# ESP32.net
KiCad netlist of a schematic drawn in Altium Designer
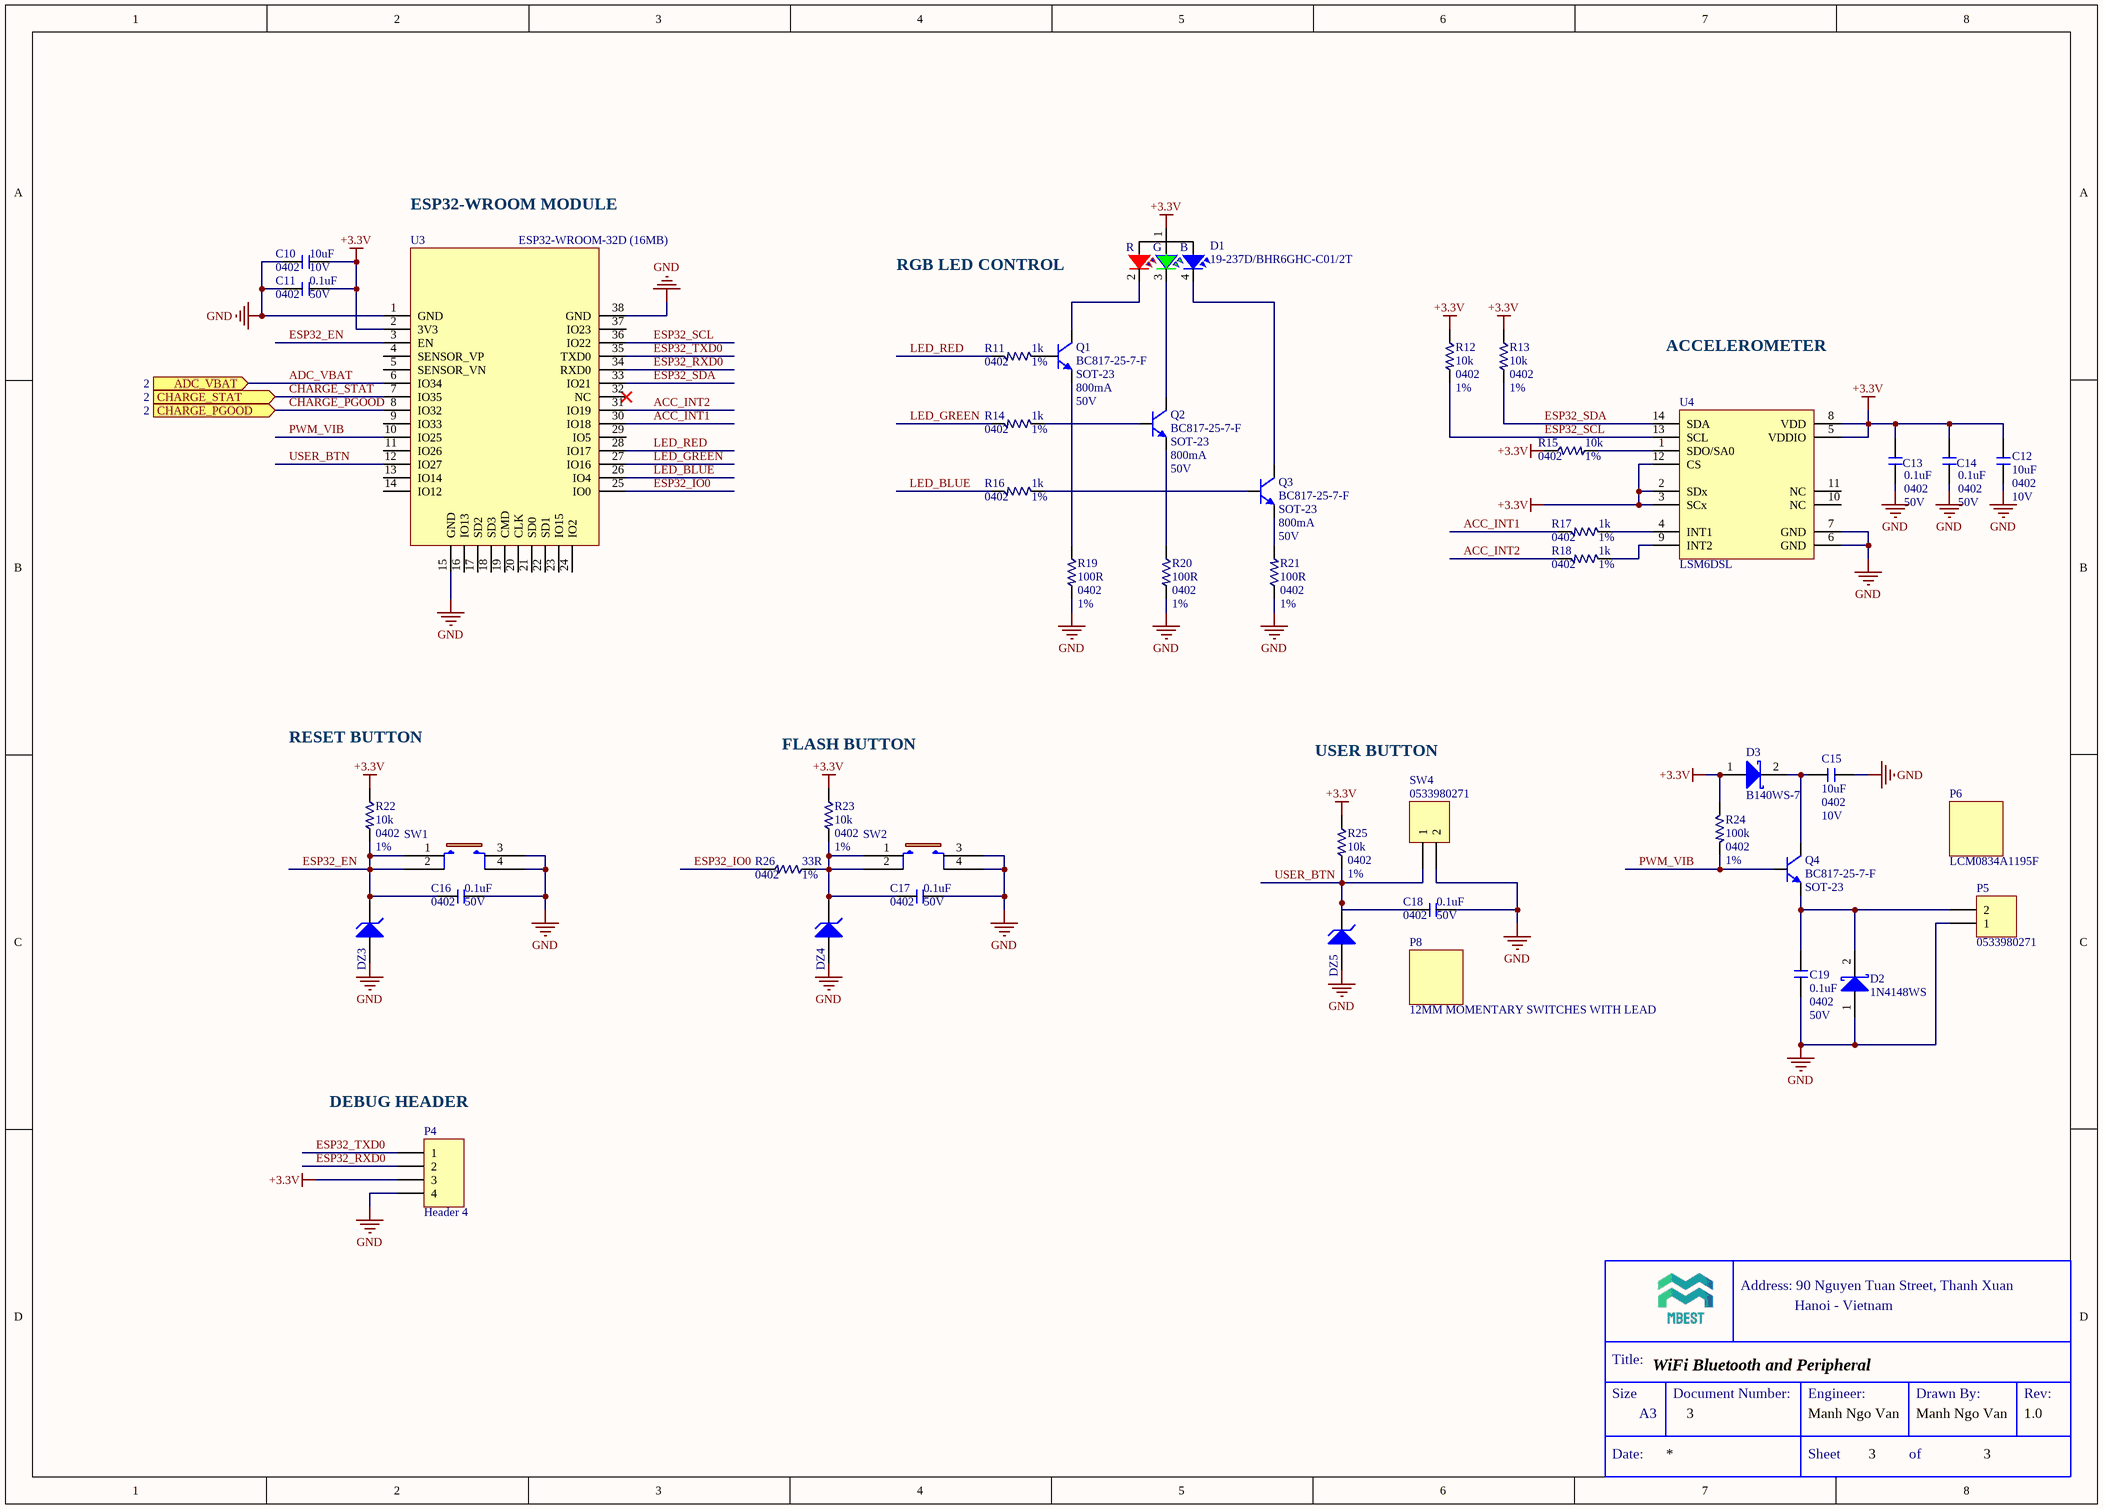
[diagram p0: ESP32.SchDoc]

(export (version "E")
  (design (tool "Eeschema 10.0.6"))
  (components
    (comp (ref "C10")
      (value "10uF")
      (footprint "C0402M")
      (description "CAP CER 10UF 10V X5R 0402")
      (fields
        (field (name "CASE/PACKAGE") "0402")
        (field (name "VOLTAGE RATING") "10V")
        (field (name "TOLERANCE") "20%")
      )
      (libsource (lib "") (part "CAP_CER_1"))
    )
    (comp (ref "C11")
      (value "0.1uF")
      (footprint "C0402M")
      (description "CAP CER 0.1UF 50V X7R 0402")
      (fields
        (field (name "MANUFACTURER") "Murata")
        (field (name "MANUFACTURER PART NUMBER") "GRM155R71H104KE14D")
        (field (name "CASE/PACKAGE") "0402")
        (field (name "VOLTAGE") "50V")
      )
      (libsource (lib "CommonLib") (part "CAP_CER"))
    )
    (comp (ref "C12")
      (value "10uF")
      (footprint "C0402M")
      (description "CAP CER 10UF 10V X5R 0402")
      (fields
        (field (name "CASE/PACKAGE") "0402")
        (field (name "VOLTAGE RATING") "10V")
        (field (name "TOLERANCE") "20%")
      )
      (libsource (lib "") (part "CAP_CER_1"))
    )
    (comp (ref "C13")
      (value "0.1uF")
      (footprint "C0402M")
      (description "CAP CER 0.1UF 50V X7R 0402")
      (fields
        (field (name "MANUFACTURER") "Murata")
        (field (name "MANUFACTURER PART NUMBER") "GRM155R71H104KE14D")
        (field (name "CASE/PACKAGE") "0402")
        (field (name "VOLTAGE") "50V")
      )
      (libsource (lib "CommonLib") (part "CAP_CER"))
    )
    (comp (ref "C14")
      (value "0.1uF")
      (footprint "C0402M")
      (description "CAP CER 0.1UF 50V X7R 0402")
      (fields
        (field (name "MANUFACTURER") "Murata")
        (field (name "MANUFACTURER PART NUMBER") "GRM155R71H104KE14D")
        (field (name "CASE/PACKAGE") "0402")
        (field (name "VOLTAGE") "50V")
      )
      (libsource (lib "CommonLib") (part "CAP_CER"))
    )
    (comp (ref "C15")
      (value "10uF")
      (footprint "C0402M")
      (description "CAP CER 10UF 10V X5R 0402")
      (fields
        (field (name "CASE/PACKAGE") "0402")
        (field (name "VOLTAGE RATING") "10V")
        (field (name "TOLERANCE") "20%")
      )
      (libsource (lib "") (part "CAP_CER_1"))
    )
    (comp (ref "C16")
      (value "0.1uF")
      (footprint "C0402M")
      (description "CAP CER 0.1UF 50V X7R 0402")
      (fields
        (field (name "MANUFACTURER") "Murata")
        (field (name "MANUFACTURER PART NUMBER") "GRM155R71H104KE14D")
        (field (name "CASE/PACKAGE") "0402")
        (field (name "VOLTAGE") "50V")
      )
      (libsource (lib "CommonLib") (part "CAP_CER"))
    )
    (comp (ref "C17")
      (value "0.1uF")
      (footprint "C0402M")
      (description "CAP CER 0.1UF 50V X7R 0402")
      (fields
        (field (name "MANUFACTURER") "Murata")
        (field (name "MANUFACTURER PART NUMBER") "GRM155R71H104KE14D")
        (field (name "CASE/PACKAGE") "0402")
        (field (name "VOLTAGE") "50V")
      )
      (libsource (lib "CommonLib") (part "CAP_CER"))
    )
    (comp (ref "C18")
      (value "0.1uF")
      (footprint "C0402M")
      (description "CAP CER 0.1UF 50V X7R 0402")
      (fields
        (field (name "MANUFACTURER") "Murata")
        (field (name "MANUFACTURER PART NUMBER") "GRM155R71H104KE14D")
        (field (name "CASE/PACKAGE") "0402")
        (field (name "VOLTAGE") "50V")
      )
      (libsource (lib "CommonLib") (part "CAP_CER"))
    )
    (comp (ref "C19")
      (value "0.1uF")
      (footprint "C0402M")
      (description "CAP CER 0.1UF 50V X7R 0402")
      (fields
        (field (name "MANUFACTURER") "Murata")
        (field (name "MANUFACTURER PART NUMBER") "GRM155R71H104KE14D")
        (field (name "CASE/PACKAGE") "0402")
        (field (name "VOLTAGE") "50V")
      )
      (libsource (lib "CommonLib") (part "CAP_CER"))
    )
    (comp (ref "D1")
      (value "19-237D/BHR6GHC-C01/2T")
      (footprint "19-237D/BHR6GHC-C01/2T")
      (description "LED RGB CLEAR 4SMD")
      (libsource (lib "SmartHome") (part "19-237D/BHR6GHC-C01/2T"))
    )
    (comp (ref "D2")
      (value "1N4148WS")
      (footprint "SODFL250X70-2N")
      (description "DIODE GEN PURP 75V 150MA SOD323F")
      (fields (field (name "MANUFACTURER") "ON Semiconductor / Fairchild"))
      (libsource (lib "CommonLib") (part "D Schottky"))
    )
    (comp (ref "D3")
      (value "B140WS-7")
      (footprint "SODFL250X70-2N")
      (description "DIODE SCHOTTKY 40V 1A SOD323")
      (libsource (lib "CommonLib") (part "D Schottky"))
    )
    (comp (ref "DZ3")
      (value "TPD1E10B06DPYR")
      (footprint "R0402M")
      (description "TVS DIODE 5.5V 14V 2X1SON")
      (fields (field (name "MANUFACTURER") "Texas Instruments"))
      (libsource (lib "CommonLib") (part "D Zener"))
    )
    (comp (ref "DZ4")
      (value "TPD1E10B06DPYR")
      (footprint "R0402M")
      (description "TVS DIODE 5.5V 14V 2X1SON")
      (fields (field (name "MANUFACTURER") "Texas Instruments"))
      (libsource (lib "CommonLib") (part "D Zener"))
    )
    (comp (ref "DZ5")
      (value "TPD1E10B06DPYR")
      (footprint "R0402M")
      (description "TVS DIODE 5.5V 14V 2X1SON")
      (fields (field (name "MANUFACTURER") "Texas Instruments"))
      (libsource (lib "CommonLib") (part "D Zener"))
    )
    (comp (ref "P4")
      (value "Header 4")
      (footprint "HDR1X4")
      (description "Header, 4-Pin")
      (fields (field (name "PUBLISHER") "Altium Limited"))
      (libsource (lib "Miscellaneous Connectors") (part "Header 4"))
    )
    (comp (ref "P5")
      (value "0533980271")
      (footprint "0533980271")
      (description "CONN HEADER SMD 2POS 1.25MM")
      (fields (field (name "PUBLISHER") "Altium Limited"))
      (libsource (lib "Miscellaneous Connectors") (part "Header 2"))
    )
    (comp (ref "P6")
      (value "LCM0834A1195F")
      (description "Coin Type Vibration Motor")
      (libsource (lib "CommonLib") (part "ADDITION"))
    )
    (comp (ref "P8")
      (value "12MM MOMENTARY SWITCHES WITH LEAD")
      (libsource (lib "CommonLib") (part "ADDITION"))
    )
    (comp (ref "Q1")
      (value "BC817-25-7-F")
      (footprint "SOT95P245X110-3N")
      (description "TRANS NPN 45V 500MA SOT23-3")
      (fields
        (field (name "CASE/PACKAGE") "SOT-23")
        (field (name "MAX COLLECTOR CURRENT") "800mA")
        (field (name "COLLECTOR BASE VOLTAGE (VCBO)") "50V")
        (field (name "MANUFACTURER") "Diodes")
      )
      (libsource (lib "SmartAC") (part "MMBT3904-7-F"))
    )
    (comp (ref "Q2")
      (value "BC817-25-7-F")
      (footprint "SOT95P245X110-3N")
      (description "TRANS NPN 45V 500MA SOT23-3")
      (fields
        (field (name "CASE/PACKAGE") "SOT-23")
        (field (name "MAX COLLECTOR CURRENT") "800mA")
        (field (name "COLLECTOR BASE VOLTAGE (VCBO)") "50V")
        (field (name "MANUFACTURER") "Diodes")
      )
      (libsource (lib "SmartAC") (part "MMBT3904-7-F"))
    )
    (comp (ref "Q3")
      (value "BC817-25-7-F")
      (footprint "SOT95P245X110-3N")
      (description "TRANS NPN 45V 500MA SOT23-3")
      (fields
        (field (name "CASE/PACKAGE") "SOT-23")
        (field (name "MAX COLLECTOR CURRENT") "800mA")
        (field (name "COLLECTOR BASE VOLTAGE (VCBO)") "50V")
        (field (name "MANUFACTURER") "Diodes")
      )
      (libsource (lib "SmartAC") (part "MMBT3904-7-F"))
    )
    (comp (ref "Q4")
      (value "BC817-25-7-F")
      (footprint "SOT95P245X110-3N")
      (description "TRANS NPN 45V 500MA SOT23-3")
      (fields (field (name "CASE/PACKAGE") "SOT-23") (field (name "MANUFACTURER") "Diodes"))
      (libsource (lib "SmartAC") (part "MMBT3904-7-F"))
    )
    (comp (ref "R11")
      (value "1k")
      (footprint "R0402M")
      (description "RES SMD 1K OHM 1% 1/16W 0402")
      (fields (field (name "CASE/PACKAGE") "0402") (field (name "TOLERANCE") "1%"))
      (libsource (lib "CommonLib") (part "RES_SMD"))
    )
    (comp (ref "R12")
      (value "10k")
      (footprint "R0402M")
      (description "RES SMD 10K OHM 1% 1/16W 0402")
      (fields
        (field (name "MANUFACTURER") "Yageo")
        (field (name "MANUFACTURER PART NUMBER") "RC0402FR-0710KL")
        (field (name "CASE CODE (IMPERIAL)") "0402")
        (field (name "TOLERANCE") "1%")
      )
      (libsource (lib "CommonLib") (part "RES_SMD"))
    )
    (comp (ref "R13")
      (value "10k")
      (footprint "R0402M")
      (description "RES SMD 10K OHM 1% 1/16W 0402")
      (fields
        (field (name "MANUFACTURER") "Yageo")
        (field (name "MANUFACTURER PART NUMBER") "RC0402FR-0710KL")
        (field (name "CASE CODE (IMPERIAL)") "0402")
        (field (name "TOLERANCE") "1%")
      )
      (libsource (lib "CommonLib") (part "RES_SMD"))
    )
    (comp (ref "R14")
      (value "1k")
      (footprint "R0402M")
      (description "RES SMD 1K OHM 1% 1/16W 0402")
      (fields (field (name "CASE/PACKAGE") "0402") (field (name "TOLERANCE") "1%"))
      (libsource (lib "CommonLib") (part "RES_SMD"))
    )
    (comp (ref "R15")
      (value "10k")
      (footprint "R0402M")
      (description "RES SMD 10K OHM 1% 1/16W 0402")
      (fields
        (field (name "MANUFACTURER") "Yageo")
        (field (name "MANUFACTURER PART NUMBER") "RC0402FR-0710KL")
        (field (name "CASE CODE (IMPERIAL)") "0402")
        (field (name "TOLERANCE") "1%")
      )
      (libsource (lib "CommonLib") (part "RES_SMD"))
    )
    (comp (ref "R16")
      (value "1k")
      (footprint "R0402M")
      (description "RES SMD 1K OHM 1% 1/16W 0402")
      (fields (field (name "CASE/PACKAGE") "0402") (field (name "TOLERANCE") "1%"))
      (libsource (lib "CommonLib") (part "RES_SMD"))
    )
    (comp (ref "R17")
      (value "1k")
      (footprint "R0402M")
      (description "RES SMD 1K OHM 1% 1/16W 0402")
      (fields (field (name "CASE/PACKAGE") "0402") (field (name "TOLERANCE") "1%"))
      (libsource (lib "CommonLib") (part "RES_SMD"))
    )
    (comp (ref "R18")
      (value "1k")
      (footprint "R0402M")
      (description "RES SMD 1K OHM 1% 1/16W 0402")
      (fields (field (name "CASE/PACKAGE") "0402") (field (name "TOLERANCE") "1%"))
      (libsource (lib "CommonLib") (part "RES_SMD"))
    )
    (comp (ref "R19")
      (value "100R")
      (footprint "R0402M")
      (description "RES SMD 100 OHM 1% 1/16W 0402")
      (fields (field (name "CASE CODE (IMPERIAL)") "0402") (field (name "TOLERANCE") "1%"))
      (libsource (lib "CommonLib") (part "RES_SMD"))
    )
    (comp (ref "R20")
      (value "100R")
      (footprint "R0402M")
      (description "RES SMD 100 OHM 1% 1/16W 0402")
      (fields (field (name "CASE CODE (IMPERIAL)") "0402") (field (name "TOLERANCE") "1%"))
      (libsource (lib "CommonLib") (part "RES_SMD"))
    )
    (comp (ref "R21")
      (value "100R")
      (footprint "R0402M")
      (description "RES SMD 100 OHM 1% 1/16W 0402")
      (fields (field (name "CASE CODE (IMPERIAL)") "0402") (field (name "TOLERANCE") "1%"))
      (libsource (lib "CommonLib") (part "RES_SMD"))
    )
    (comp (ref "R22")
      (value "10k")
      (footprint "R0402M")
      (description "RES SMD 10K OHM 1% 1/16W 0402")
      (fields
        (field (name "MANUFACTURER") "Yageo")
        (field (name "MANUFACTURER PART NUMBER") "RC0402FR-0710KL")
        (field (name "CASE CODE (IMPERIAL)") "0402")
        (field (name "TOLERANCE") "1%")
      )
      (libsource (lib "CommonLib") (part "RES_SMD"))
    )
    (comp (ref "R23")
      (value "10k")
      (footprint "R0402M")
      (description "RES SMD 10K OHM 1% 1/16W 0402")
      (fields
        (field (name "MANUFACTURER") "Yageo")
        (field (name "MANUFACTURER PART NUMBER") "RC0402FR-0710KL")
        (field (name "CASE CODE (IMPERIAL)") "0402")
        (field (name "TOLERANCE") "1%")
      )
      (libsource (lib "CommonLib") (part "RES_SMD"))
    )
    (comp (ref "R24")
      (value "100k")
      (footprint "R0402M")
      (description "RES SMD 100K OHM 1% 1/16W 0402")
      (fields
        (field (name "MANUFACTURER") "Yageo")
        (field (name "MANUFACTURER PART NUMBER") "RC0402FR-07100KL")
        (field (name "CASE/PACKAGE") "0402")
        (field (name "TOLERANCE") "1%")
      )
      (libsource (lib "BLE1") (part "RES_SMD"))
    )
    (comp (ref "R25")
      (value "10k")
      (footprint "R0402M")
      (description "RES SMD 10K OHM 1% 1/16W 0402")
      (fields
        (field (name "MANUFACTURER") "Yageo")
        (field (name "MANUFACTURER PART NUMBER") "RC0402FR-0710KL")
        (field (name "CASE CODE (IMPERIAL)") "0402")
        (field (name "TOLERANCE") "1%")
      )
      (libsource (lib "CommonLib") (part "RES_SMD"))
    )
    (comp (ref "R26")
      (value "33R")
      (footprint "R0402M")
      (description "RES SMD 33 OHM 1% 1/16W 0402")
      (fields (field (name "SIZE CODE") "0402") (field (name "TOLERANCE") "1%"))
      (libsource (lib "CommonLib") (part "RES_SMD"))
    )
    (comp (ref "SW1")
      (value "PTS810SJK250SMTRLFS")
      (footprint "PTS810SJG250SMTRLFS")
      (description "SWITCH TACTILE SPST-NO 0.05A 16V")
      (fields
        (field (name "MANUFACTURER") "C&K")
        (field (name "MANUFACTURER PART NUMBER") "PTS810 SJK 250 SMTR LFS")
      )
      (libsource (lib "AltiumDbLib") (part "PUSHBUTTON1"))
    )
    (comp (ref "SW2")
      (value "PTS810SJK250SMTRLFS")
      (footprint "PTS810SJG250SMTRLFS")
      (description "SWITCH TACTILE SPST-NO 0.05A 16V")
      (fields
        (field (name "MANUFACTURER") "C&K")
        (field (name "MANUFACTURER PART NUMBER") "PTS810 SJK 250 SMTR LFS")
      )
      (libsource (lib "AltiumDbLib") (part "PUSHBUTTON1"))
    )
    (comp (ref "SW4")
      (value "0533980271")
      (footprint "0533980271")
      (description "CONN HEADER SMD 2POS 1.25MM")
      (fields (field (name "PUBLISHER") "Altium Limited"))
      (libsource (lib "Miscellaneous Connectors") (part "Header 2"))
    )
    (comp (ref "U3")
      (value "ESP32-WROOM-32D (16MB)")
      (footprint "ESP32S")
      (description "RX TXRX MOD WIFI TRACE ANT SMD")
      (fields (field (name "MANUFACTURER") "Espressif Systems"))
      (libsource (lib "BLE") (part "ESP32-S"))
    )
    (comp (ref "U4")
      (value "LSM6DSL")
      (footprint "LSM6DSL")
      (description "IMU ACCEL/GYRO I2C/SPI 14LGA")
      (libsource (lib "SmartHome") (part "LSM6DSL"))
    )
  )
  (nets
    (net (code "1") (name "+3.3V") (class "Default")
      (node (ref "C10") (pin "2") (pinfunction "2_2") (pintype "passive"))
      (node (ref "C11") (pin "2") (pinfunction "2_2") (pintype "passive"))
      (node (ref "C12") (pin "2") (pinfunction "2_2") (pintype "passive"))
      (node (ref "C13") (pin "2") (pinfunction "2_2") (pintype "passive"))
      (node (ref "C14") (pin "2") (pinfunction "2_2") (pintype "passive"))
      (node (ref "D1") (pin "1") (pinfunction "ANODE_1") (pintype "power_in"))
      (node (ref "D3") (pin "1") (pinfunction "A_1") (pintype "passive"))
      (node (ref "P4") (pin "3") (pinfunction "3_3") (pintype "passive"))
      (node (ref "R12") (pin "2") (pinfunction "2_2") (pintype "passive"))
      (node (ref "R13") (pin "2") (pinfunction "2_2") (pintype "passive"))
      (node (ref "R15") (pin "2") (pinfunction "2_2") (pintype "passive"))
      (node (ref "R22") (pin "2") (pinfunction "2_2") (pintype "passive"))
      (node (ref "R23") (pin "2") (pinfunction "2_2") (pintype "passive"))
      (node (ref "R24") (pin "2") (pinfunction "2_2") (pintype "passive"))
      (node (ref "R25") (pin "2") (pinfunction "2_2") (pintype "passive"))
      (node (ref "U3") (pin "2") (pinfunction "3V3_2") (pintype "passive"))
      (node (ref "U4") (pin "12") (pinfunction "CS_12") (pintype "passive"))
      (node (ref "U4") (pin "2") (pinfunction "SDx_2") (pintype "passive"))
      (node (ref "U4") (pin "3") (pinfunction "SCx_3") (pintype "passive"))
      (node (ref "U4") (pin "5") (pinfunction "VDDIO_5") (pintype "passive"))
      (node (ref "U4") (pin "8") (pinfunction "VDD_8") (pintype "passive"))
    )
    (net (code "2") (name "/ACC_INT1") (class "Default")
      (node (ref "R17") (pin "1") (pinfunction "1_1") (pintype "passive"))
      (node (ref "U3") (pin "30") (pinfunction "IO18_30") (pintype "passive"))
    )
    (net (code "3") (name "/ACC_INT2") (class "Default")
      (node (ref "R18") (pin "1") (pinfunction "1_1") (pintype "passive"))
      (node (ref "U3") (pin "31") (pinfunction "IO19_31") (pintype "passive"))
    )
    (net (code "4") (name "/ADC_VBAT") (class "Default")
      (node (ref "U3") (pin "6") (pinfunction "IO34_6") (pintype "passive"))
    )
    (net (code "5") (name "/CHARGE_PGOOD") (class "Default")
      (node (ref "U3") (pin "8") (pinfunction "IO32_8") (pintype "passive"))
    )
    (net (code "6") (name "/CHARGE_STAT") (class "Default")
      (node (ref "U3") (pin "7") (pinfunction "IO35_7") (pintype "passive"))
    )
    (net (code "7") (name "/ESP32_EN") (class "Default")
      (node (ref "C16") (pin "1") (pinfunction "1_1") (pintype "passive"))
      (node (ref "DZ3") (pin "2") (pinfunction "K_2") (pintype "passive"))
      (node (ref "R22") (pin "1") (pinfunction "1_1") (pintype "passive"))
      (node (ref "SW1") (pin "1") (pinfunction "1_1") (pintype "passive"))
      (node (ref "SW1") (pin "2") (pinfunction "2_2") (pintype "passive"))
      (node (ref "U3") (pin "3") (pinfunction "EN_3") (pintype "passive"))
    )
    (net (code "8") (name "/ESP32_IO0") (class "Default")
      (node (ref "R26") (pin "1") (pinfunction "1_1") (pintype "passive"))
      (node (ref "U3") (pin "25") (pinfunction "IO0_25") (pintype "passive"))
    )
    (net (code "9") (name "/ESP32_RXD0") (class "Default")
      (node (ref "P4") (pin "2") (pinfunction "2_2") (pintype "passive"))
      (node (ref "U3") (pin "34") (pinfunction "RXD0_34") (pintype "passive"))
    )
    (net (code "10") (name "/ESP32_SCL") (class "Default")
      (node (ref "R12") (pin "1") (pinfunction "1_1") (pintype "passive"))
      (node (ref "U3") (pin "36") (pinfunction "IO22_36") (pintype "passive"))
      (node (ref "U4") (pin "13") (pinfunction "SCL_13") (pintype "passive"))
    )
    (net (code "11") (name "/ESP32_SDA") (class "Default")
      (node (ref "R13") (pin "1") (pinfunction "1_1") (pintype "passive"))
      (node (ref "U3") (pin "33") (pinfunction "IO21_33") (pintype "passive"))
      (node (ref "U4") (pin "14") (pinfunction "SDA_14") (pintype "passive"))
    )
    (net (code "12") (name "/ESP32_TXD0") (class "Default")
      (node (ref "P4") (pin "1") (pinfunction "1_1") (pintype "passive"))
      (node (ref "U3") (pin "35") (pinfunction "TXD0_35") (pintype "passive"))
    )
    (net (code "13") (name "/LED_BLUE") (class "Default")
      (node (ref "R16") (pin "1") (pinfunction "1_1") (pintype "passive"))
      (node (ref "U3") (pin "26") (pinfunction "IO4_26") (pintype "passive"))
    )
    (net (code "14") (name "/LED_GREEN") (class "Default")
      (node (ref "R14") (pin "1") (pinfunction "1_1") (pintype "passive"))
      (node (ref "U3") (pin "27") (pinfunction "IO16_27") (pintype "passive"))
    )
    (net (code "15") (name "/LED_RED") (class "Default")
      (node (ref "R11") (pin "1") (pinfunction "1_1") (pintype "passive"))
      (node (ref "U3") (pin "28") (pinfunction "IO17_28") (pintype "passive"))
    )
    (net (code "16") (name "/PWM_VIB") (class "Default")
      (node (ref "Q4") (pin "1") (pinfunction "B_1") (pintype "passive"))
      (node (ref "R24") (pin "1") (pinfunction "1_1") (pintype "passive"))
      (node (ref "U3") (pin "10") (pinfunction "IO25_10") (pintype "passive"))
    )
    (net (code "17") (name "/USER_BTN") (class "Default")
      (node (ref "C18") (pin "1") (pinfunction "1_1") (pintype "passive"))
      (node (ref "DZ5") (pin "2") (pinfunction "K_2") (pintype "passive"))
      (node (ref "R25") (pin "1") (pinfunction "1_1") (pintype "passive"))
      (node (ref "SW4") (pin "1") (pinfunction "1_1") (pintype "passive"))
      (node (ref "U3") (pin "12") (pinfunction "IO27_12") (pintype "passive"))
    )
    (net (code "18") (name "GND") (class "Default")
      (node (ref "C10") (pin "1") (pinfunction "1_1") (pintype "passive"))
      (node (ref "C11") (pin "1") (pinfunction "1_1") (pintype "passive"))
      (node (ref "C12") (pin "1") (pinfunction "1_1") (pintype "passive"))
      (node (ref "C13") (pin "1") (pinfunction "1_1") (pintype "passive"))
      (node (ref "C14") (pin "1") (pinfunction "1_1") (pintype "passive"))
      (node (ref "C15") (pin "1") (pinfunction "1_1") (pintype "passive"))
      (node (ref "C16") (pin "2") (pinfunction "2_2") (pintype "passive"))
      (node (ref "C17") (pin "2") (pinfunction "2_2") (pintype "passive"))
      (node (ref "C18") (pin "2") (pinfunction "2_2") (pintype "passive"))
      (node (ref "C19") (pin "1") (pinfunction "1_1") (pintype "passive"))
      (node (ref "D2") (pin "1") (pinfunction "A_1") (pintype "passive"))
      (node (ref "DZ3") (pin "1") (pinfunction "A_1") (pintype "passive"))
      (node (ref "DZ4") (pin "1") (pinfunction "A_1") (pintype "passive"))
      (node (ref "DZ5") (pin "1") (pinfunction "A_1") (pintype "passive"))
      (node (ref "P4") (pin "4") (pinfunction "4_4") (pintype "passive"))
      (node (ref "P5") (pin "1") (pinfunction "1_1") (pintype "passive"))
      (node (ref "R19") (pin "1") (pinfunction "1_1") (pintype "passive"))
      (node (ref "R20") (pin "1") (pinfunction "1_1") (pintype "passive"))
      (node (ref "R21") (pin "2") (pinfunction "2_2") (pintype "passive"))
      (node (ref "SW1") (pin "3") (pinfunction "3_3") (pintype "passive"))
      (node (ref "SW1") (pin "4") (pinfunction "4_4") (pintype "passive"))
      (node (ref "SW2") (pin "3") (pinfunction "3_3") (pintype "passive"))
      (node (ref "SW2") (pin "4") (pinfunction "4_4") (pintype "passive"))
      (node (ref "SW4") (pin "2") (pinfunction "2_2") (pintype "passive"))
      (node (ref "U3") (pin "1") (pinfunction "GND_1") (pintype "passive"))
      (node (ref "U3") (pin "15") (pinfunction "GND_15") (pintype "passive"))
      (node (ref "U3") (pin "38") (pinfunction "GND_38") (pintype "passive"))
      (node (ref "U4") (pin "6") (pinfunction "GND_6") (pintype "passive"))
      (node (ref "U4") (pin "7") (pinfunction "GND_7") (pintype "passive"))
    )
    (net (code "19") (name "Net-(D1-B)") (class "Default")
      (node (ref "D1") (pin "4") (pinfunction "B_4") (pintype "power_in"))
      (node (ref "Q3") (pin "3") (pinfunction "C_3") (pintype "passive"))
    )
    (net (code "20") (name "Net-(D1-G)") (class "Default")
      (node (ref "D1") (pin "3") (pinfunction "G_3") (pintype "power_in"))
      (node (ref "Q2") (pin "3") (pinfunction "C_3") (pintype "passive"))
    )
    (net (code "21") (name "Net-(D1-R)") (class "Default")
      (node (ref "D1") (pin "2") (pinfunction "R_2") (pintype "power_in"))
      (node (ref "Q1") (pin "3") (pinfunction "C_3") (pintype "passive"))
    )
    (net (code "22") (name "Net-(D2-K)") (class "Default")
      (node (ref "C19") (pin "2") (pinfunction "2_2") (pintype "passive"))
      (node (ref "D2") (pin "2") (pinfunction "K_2") (pintype "passive"))
      (node (ref "P5") (pin "2") (pinfunction "2_2") (pintype "passive"))
      (node (ref "Q4") (pin "2") (pinfunction "E_2") (pintype "passive"))
    )
    (net (code "23") (name "Net-(D3-K)") (class "Default")
      (node (ref "C15") (pin "2") (pinfunction "2_2") (pintype "passive"))
      (node (ref "D3") (pin "2") (pinfunction "K_2") (pintype "passive"))
      (node (ref "Q4") (pin "3") (pinfunction "C_3") (pintype "passive"))
    )
    (net (code "24") (name "Net-(DZ4-K)") (class "Default")
      (node (ref "C17") (pin "1") (pinfunction "1_1") (pintype "passive"))
      (node (ref "DZ4") (pin "2") (pinfunction "K_2") (pintype "passive"))
      (node (ref "R23") (pin "1") (pinfunction "1_1") (pintype "passive"))
      (node (ref "R26") (pin "2") (pinfunction "2_2") (pintype "passive"))
      (node (ref "SW2") (pin "1") (pinfunction "1_1") (pintype "passive"))
      (node (ref "SW2") (pin "2") (pinfunction "2_2") (pintype "passive"))
    )
    (net (code "25") (name "Net-(Q1-B)") (class "Default")
      (node (ref "Q1") (pin "1") (pinfunction "B_1") (pintype "passive"))
      (node (ref "R11") (pin "2") (pinfunction "2_2") (pintype "passive"))
    )
    (net (code "26") (name "Net-(Q1-E)") (class "Default")
      (node (ref "Q1") (pin "2") (pinfunction "E_2") (pintype "passive"))
      (node (ref "R19") (pin "2") (pinfunction "2_2") (pintype "passive"))
    )
    (net (code "27") (name "Net-(Q2-B)") (class "Default")
      (node (ref "Q2") (pin "1") (pinfunction "B_1") (pintype "passive"))
      (node (ref "R14") (pin "2") (pinfunction "2_2") (pintype "passive"))
    )
    (net (code "28") (name "Net-(Q2-E)") (class "Default")
      (node (ref "Q2") (pin "2") (pinfunction "E_2") (pintype "passive"))
      (node (ref "R20") (pin "2") (pinfunction "2_2") (pintype "passive"))
    )
    (net (code "29") (name "Net-(Q3-B)") (class "Default")
      (node (ref "Q3") (pin "1") (pinfunction "B_1") (pintype "passive"))
      (node (ref "R16") (pin "2") (pinfunction "2_2") (pintype "passive"))
    )
    (net (code "30") (name "Net-(Q3-E)") (class "Default")
      (node (ref "Q3") (pin "2") (pinfunction "E_2") (pintype "passive"))
      (node (ref "R21") (pin "1") (pinfunction "1_1") (pintype "passive"))
    )
    (net (code "31") (name "Net-(U4-INT1)") (class "Default")
      (node (ref "R17") (pin "2") (pinfunction "2_2") (pintype "passive"))
      (node (ref "U4") (pin "4") (pinfunction "INT1_4") (pintype "passive"))
    )
    (net (code "32") (name "Net-(U4-INT2)") (class "Default")
      (node (ref "R18") (pin "2") (pinfunction "2_2") (pintype "passive"))
      (node (ref "U4") (pin "9") (pinfunction "INT2_9") (pintype "passive"))
    )
    (net (code "33") (name "Net-(U4-SDO{slash}SA0)") (class "Default")
      (node (ref "R15") (pin "1") (pinfunction "1_1") (pintype "passive"))
      (node (ref "U4") (pin "1") (pinfunction "SDO/SA0_1") (pintype "passive"))
    )
    (net (code "34") (name "unconnected-(U3-CLK-Pad20)") (class "Default")
      (node (ref "U3") (pin "20") (pinfunction "CLK_20") (pintype "passive"))
    )
    (net (code "35") (name "unconnected-(U3-CMD-Pad19)") (class "Default")
      (node (ref "U3") (pin "19") (pinfunction "CMD_19") (pintype "passive"))
    )
    (net (code "36") (name "unconnected-(U3-IO2-Pad24)") (class "Default")
      (node (ref "U3") (pin "24") (pinfunction "IO2_24") (pintype "passive"))
    )
    (net (code "37") (name "unconnected-(U3-IO5-Pad29)") (class "Default")
      (node (ref "U3") (pin "29") (pinfunction "IO5_29") (pintype "passive"))
    )
    (net (code "38") (name "unconnected-(U3-IO12-Pad14)") (class "Default")
      (node (ref "U3") (pin "14") (pinfunction "IO12_14") (pintype "passive"))
    )
    (net (code "39") (name "unconnected-(U3-IO13-Pad16)") (class "Default")
      (node (ref "U3") (pin "16") (pinfunction "IO13_16") (pintype "passive"))
    )
    (net (code "40") (name "unconnected-(U3-IO14-Pad13)") (class "Default")
      (node (ref "U3") (pin "13") (pinfunction "IO14_13") (pintype "passive"))
    )
    (net (code "41") (name "unconnected-(U3-IO15-Pad23)") (class "Default")
      (node (ref "U3") (pin "23") (pinfunction "IO15_23") (pintype "passive"))
    )
    (net (code "42") (name "unconnected-(U3-IO23-Pad37)") (class "Default")
      (node (ref "U3") (pin "37") (pinfunction "IO23_37") (pintype "passive"))
    )
    (net (code "43") (name "unconnected-(U3-IO26-Pad11)") (class "Default")
      (node (ref "U3") (pin "11") (pinfunction "IO26_11") (pintype "passive"))
    )
    (net (code "44") (name "unconnected-(U3-IO33-Pad9)") (class "Default")
      (node (ref "U3") (pin "9") (pinfunction "IO33_9") (pintype "passive"))
    )
    (net (code "45") (name "unconnected-(U3-NC-Pad32)") (class "Default")
      (node (ref "U3") (pin "32") (pinfunction "NC_32") (pintype "passive+no_connect"))
    )
    (net (code "46") (name "unconnected-(U3-SD0-Pad21)") (class "Default")
      (node (ref "U3") (pin "21") (pinfunction "SD0_21") (pintype "passive"))
    )
    (net (code "47") (name "unconnected-(U3-SD1-Pad22)") (class "Default")
      (node (ref "U3") (pin "22") (pinfunction "SD1_22") (pintype "passive"))
    )
    (net (code "48") (name "unconnected-(U3-SD2-Pad17)") (class "Default")
      (node (ref "U3") (pin "17") (pinfunction "SD2_17") (pintype "passive"))
    )
    (net (code "49") (name "unconnected-(U3-SD3-Pad18)") (class "Default")
      (node (ref "U3") (pin "18") (pinfunction "SD3_18") (pintype "passive"))
    )
    (net (code "50") (name "unconnected-(U3-SENSOR_VN-Pad5)") (class "Default")
      (node (ref "U3") (pin "5") (pinfunction "SENSOR_VN_5") (pintype "passive"))
    )
    (net (code "51") (name "unconnected-(U3-SENSOR_VP-Pad4)") (class "Default")
      (node (ref "U3") (pin "4") (pinfunction "SENSOR_VP_4") (pintype "passive"))
    )
    (net (code "52") (name "unconnected-(U4-NC-Pad10)") (class "Default")
      (node (ref "U4") (pin "10") (pinfunction "NC_10") (pintype "passive"))
    )
    (net (code "53") (name "unconnected-(U4-NC-Pad11)") (class "Default")
      (node (ref "U4") (pin "11") (pinfunction "NC_11") (pintype "passive"))
    )
  )
)
